# usb_dip_v1.net
KiCad netlist of a schematic drawn in EAGLE
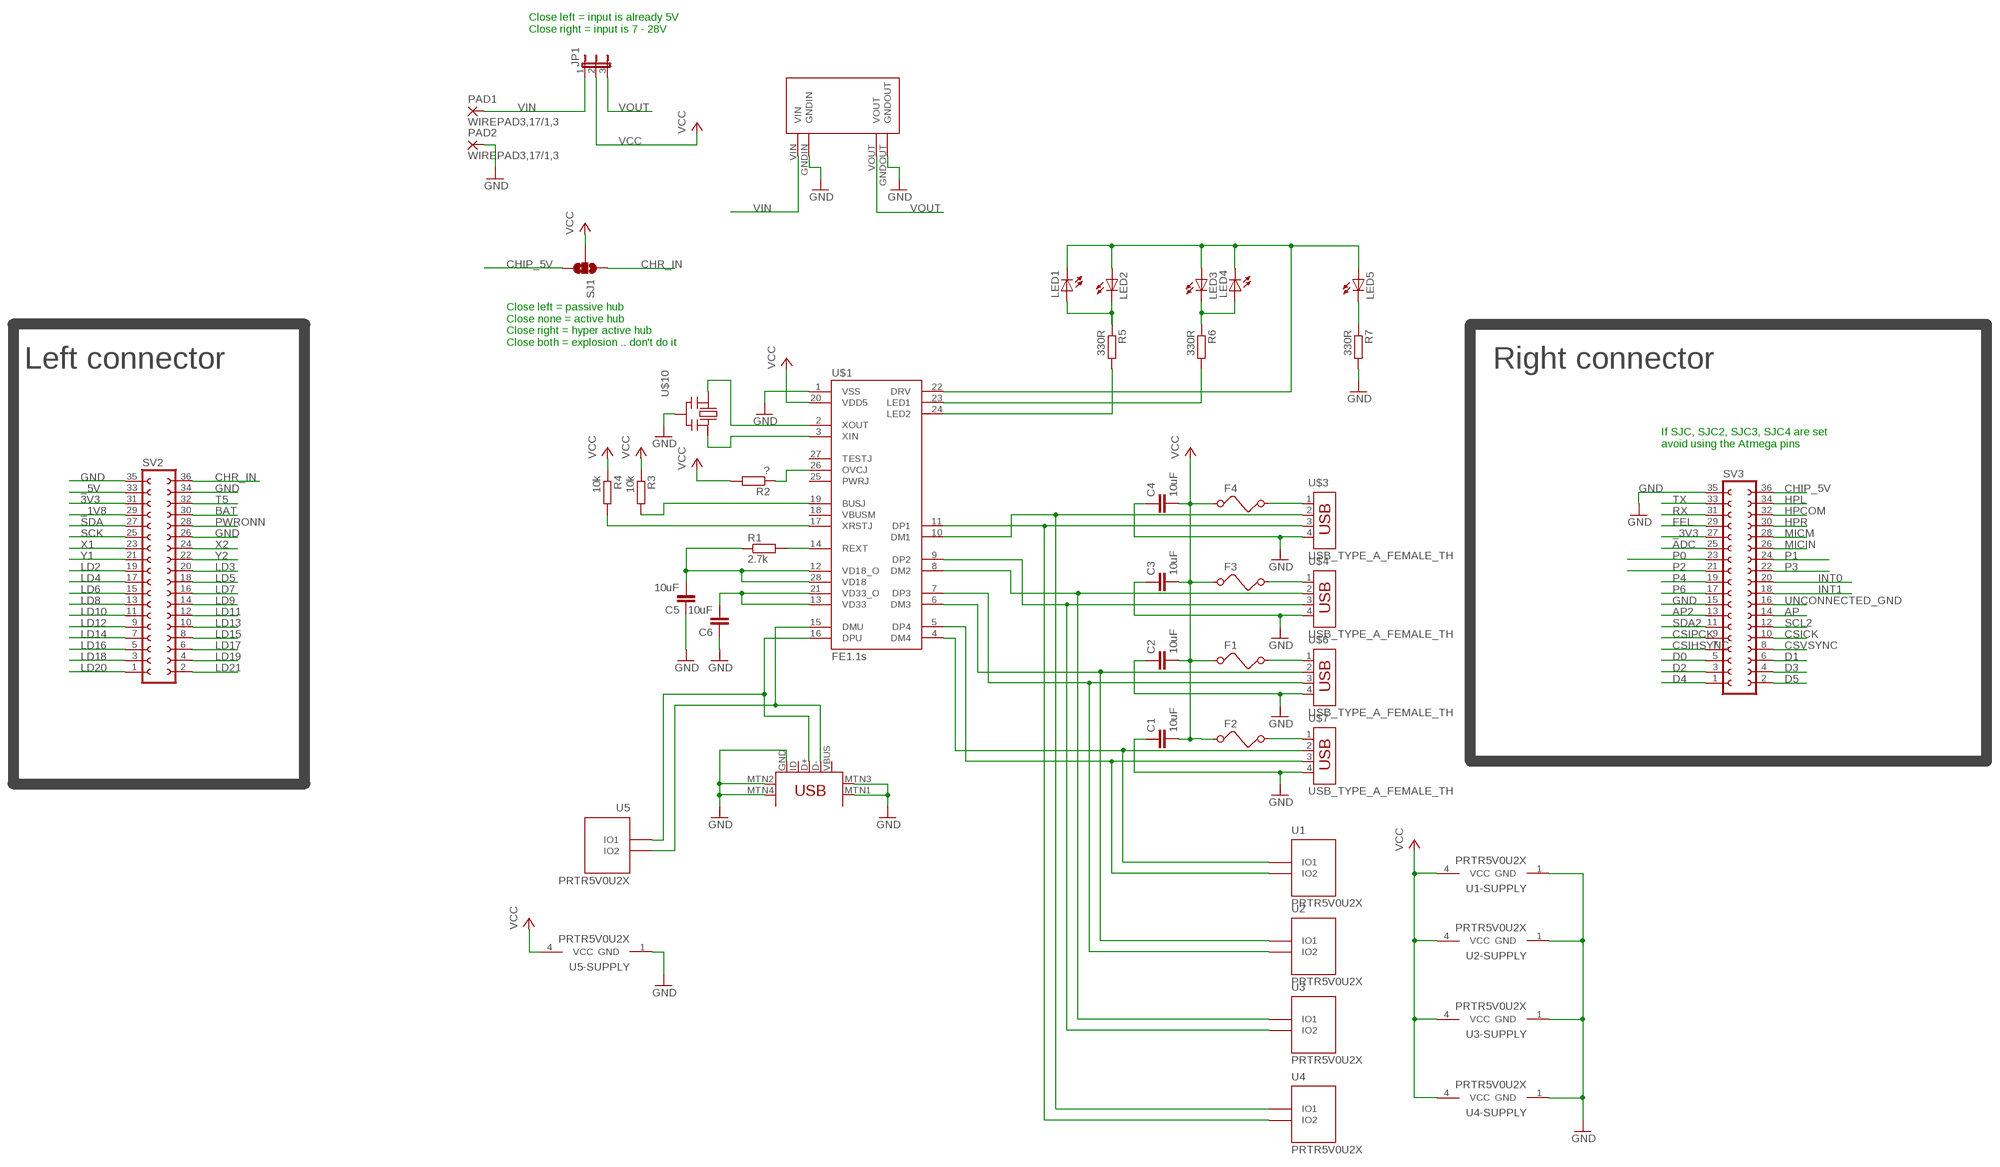
[diagram p0: schematic, sheet 1]

(export (version "E")
  (design (tool "Eeschema 10.0.6"))
  (components
    (comp (ref "C1")
      (value "10uF")
      (footprint "eagle-import:C1210")
      (libsource (lib "eagle-import") (part "C-EUC1210"))
    )
    (comp (ref "C2")
      (value "10uF")
      (footprint "eagle-import:C1210")
      (libsource (lib "eagle-import") (part "C-EUC1210"))
    )
    (comp (ref "C3")
      (value "10uF")
      (footprint "eagle-import:C1210")
      (libsource (lib "eagle-import") (part "C-EUC1210"))
    )
    (comp (ref "C4")
      (value "10uF")
      (footprint "eagle-import:C1210")
      (libsource (lib "eagle-import") (part "C-EUC1210"))
    )
    (comp (ref "C5")
      (value "10uF")
      (footprint "eagle-import:C1210")
      (libsource (lib "eagle-import") (part "C-EUC1210"))
    )
    (comp (ref "C6")
      (value "10uF")
      (footprint "eagle-import:C1210")
      (libsource (lib "eagle-import") (part "C-EUC1210"))
    )
    (comp (ref "F1")
      (value "FUSED")
      (footprint "eagle-import:1210")
      (libsource (lib "eagle-import") (part "FUSED"))
    )
    (comp (ref "F2")
      (value "FUSED")
      (footprint "eagle-import:1210")
      (libsource (lib "eagle-import") (part "FUSED"))
    )
    (comp (ref "F3")
      (value "FUSED")
      (footprint "eagle-import:1210")
      (libsource (lib "eagle-import") (part "FUSED"))
    )
    (comp (ref "F4")
      (value "FUSED")
      (footprint "eagle-import:1210")
      (libsource (lib "eagle-import") (part "FUSED"))
    )
    (comp (ref "JP1")
      (value "JP2E")
      (footprint "eagle-import:JP2")
      (libsource (lib "eagle-import") (part "JP2E"))
    )
    (comp (ref "LED1")
      (value "LEDCHIP-LED0805")
      (footprint "eagle-import:CHIP-LED0805")
      (libsource (lib "eagle-import") (part "LEDCHIP-LED0805"))
    )
    (comp (ref "LED2")
      (value "LEDCHIP-LED0805")
      (footprint "eagle-import:CHIP-LED0805")
      (libsource (lib "eagle-import") (part "LEDCHIP-LED0805"))
    )
    (comp (ref "LED3")
      (value "LEDCHIP-LED0805")
      (footprint "eagle-import:CHIP-LED0805")
      (libsource (lib "eagle-import") (part "LEDCHIP-LED0805"))
    )
    (comp (ref "LED4")
      (value "LEDCHIP-LED0805")
      (footprint "eagle-import:CHIP-LED0805")
      (libsource (lib "eagle-import") (part "LEDCHIP-LED0805"))
    )
    (comp (ref "LED5")
      (value "LEDCHIP-LED0805")
      (footprint "eagle-import:CHIP-LED0805")
      (libsource (lib "eagle-import") (part "LEDCHIP-LED0805"))
    )
    (comp (ref "PAD1")
      (value "WIREPAD3,17/1,3")
      (footprint "eagle-import:3,17_1,3")
      (libsource (lib "eagle-import") (part "WIREPAD3,17/1,3"))
    )
    (comp (ref "PAD2")
      (value "WIREPAD3,17/1,3")
      (footprint "eagle-import:3,17_1,3")
      (libsource (lib "eagle-import") (part "WIREPAD3,17/1,3"))
    )
    (comp (ref "R1")
      (value "2.7k")
      (footprint "eagle-import:R0805")
      (libsource (lib "eagle-import") (part "R-EU_R0805"))
    )
    (comp (ref "R2")
      (value "?")
      (footprint "eagle-import:R0805")
      (libsource (lib "eagle-import") (part "R-EU_R0805"))
    )
    (comp (ref "R3")
      (value "10k")
      (footprint "eagle-import:R0805")
      (libsource (lib "eagle-import") (part "R-EU_R0805"))
    )
    (comp (ref "R4")
      (value "10k")
      (footprint "eagle-import:R0805")
      (libsource (lib "eagle-import") (part "R-EU_R0805"))
    )
    (comp (ref "R5")
      (value "330R")
      (footprint "eagle-import:R0805")
      (libsource (lib "eagle-import") (part "R-EU_R0805"))
    )
    (comp (ref "R6")
      (value "330R")
      (footprint "eagle-import:R0805")
      (libsource (lib "eagle-import") (part "R-EU_R0805"))
    )
    (comp (ref "R7")
      (value "330R")
      (footprint "eagle-import:R0805")
      (libsource (lib "eagle-import") (part "R-EU_R0805"))
    )
    (comp (ref "SJ1")
      (value "SOLDERJUMPER_2WAYT")
      (footprint "eagle-import:SJ_2")
      (libsource (lib "eagle-import") (part "SOLDERJUMPER_2WAYT"))
    )
    (comp (ref "SV2")
      (value "FE18-2")
      (footprint "eagle-import:FE18-2")
      (libsource (lib "eagle-import") (part "FE18-2"))
    )
    (comp (ref "SV3")
      (value "FE18-2")
      (footprint "eagle-import:FE18-2")
      (libsource (lib "eagle-import") (part "FE18-2"))
    )
    (comp (ref "U$1")
      (value "FE1.1S")
      (footprint "eagle-import:FE1.1S_SSOP-28")
      (libsource (lib "eagle-import") (part "FE1.1S"))
    )
    (comp (ref "U$3")
      (value "USB_TYPE_A_FEMALE_TH")
      (footprint "eagle-import:USB_TYPE_A_FEMALE_TH")
      (libsource (lib "eagle-import") (part "USB_TYPE_A_FEMALE_TH"))
    )
    (comp (ref "U$4")
      (value "USB_TYPE_A_FEMALE_TH")
      (footprint "eagle-import:USB_TYPE_A_FEMALE_TH")
      (libsource (lib "eagle-import") (part "USB_TYPE_A_FEMALE_TH"))
    )
    (comp (ref "U$6")
      (value "USB_TYPE_A_FEMALE_TH")
      (footprint "eagle-import:USB_TYPE_A_FEMALE_TH")
      (libsource (lib "eagle-import") (part "USB_TYPE_A_FEMALE_TH"))
    )
    (comp (ref "U$7")
      (value "USB_TYPE_A_FEMALE_TH")
      (footprint "eagle-import:USB_TYPE_A_FEMALE_TH")
      (libsource (lib "eagle-import") (part "USB_TYPE_A_FEMALE_TH"))
    )
    (comp (ref "U$8")
      (value "USB-MINIB-5PIN")
      (footprint "eagle-import:USB-MINIB")
      (libsource (lib "eagle-import") (part "USB-MINIB-5PIN"))
    )
    (comp (ref "U$9")
      (value "MP1584EN")
      (footprint "eagle-import:MP1584EN")
      (libsource (lib "eagle-import") (part "MP1584EN"))
    )
    (comp (ref "U$10")
      (value "CERMOSCILL-THM")
      (footprint "eagle-import:CERM_OSC")
      (libsource (lib "eagle-import") (part "CERMOSCILL-THM"))
    )
    (comp (ref "U1")
      (value "PRTR5V0U2X")
      (footprint "eagle-import:SOT-143B")
      (fields
        (field (name "MANUFACTURER") "NXP Semiconductors")
        (field (name "PART_NUMBER") "PRTR5V0U2X,215")
      )
      (libsource (lib "eagle-import") (part "PRTR5V0U2X?"))
    )
    (comp (ref "U2")
      (value "PRTR5V0U2X")
      (footprint "eagle-import:SOT-143B")
      (fields
        (field (name "MANUFACTURER") "NXP Semiconductors")
        (field (name "PART_NUMBER") "PRTR5V0U2X,215")
      )
      (libsource (lib "eagle-import") (part "PRTR5V0U2X?"))
    )
    (comp (ref "U3")
      (value "PRTR5V0U2X")
      (footprint "eagle-import:SOT-143B")
      (fields
        (field (name "MANUFACTURER") "NXP Semiconductors")
        (field (name "PART_NUMBER") "PRTR5V0U2X,215")
      )
      (libsource (lib "eagle-import") (part "PRTR5V0U2X?"))
    )
    (comp (ref "U4")
      (value "PRTR5V0U2X")
      (footprint "eagle-import:SOT-143B")
      (fields
        (field (name "MANUFACTURER") "NXP Semiconductors")
        (field (name "PART_NUMBER") "PRTR5V0U2X,215")
      )
      (libsource (lib "eagle-import") (part "PRTR5V0U2X?"))
    )
    (comp (ref "U5")
      (value "PRTR5V0U2X")
      (footprint "eagle-import:SOT-143B")
      (fields
        (field (name "MANUFACTURER") "NXP Semiconductors")
        (field (name "PART_NUMBER") "PRTR5V0U2X,215")
      )
      (libsource (lib "eagle-import") (part "PRTR5V0U2X?"))
    )
  )
  (nets
    (net (code "1") (name "/3V3") (class "Default")
      (node (ref "SV2") (pin "31") (pinfunction "31_31") (pintype "passive"))
    )
    (net (code "2") (name "/ADC") (class "Default")
      (node (ref "SV3") (pin "25") (pinfunction "25_25") (pintype "passive"))
    )
    (net (code "3") (name "/AP") (class "Default")
      (node (ref "SV3") (pin "14") (pinfunction "14_14") (pintype "passive"))
    )
    (net (code "4") (name "/AP2") (class "Default")
      (node (ref "SV3") (pin "13") (pinfunction "13_13") (pintype "passive"))
    )
    (net (code "5") (name "/BAT") (class "Default")
      (node (ref "SV2") (pin "30") (pinfunction "30_30") (pintype "passive"))
    )
    (net (code "6") (name "/CHIP_5V") (class "Default")
      (node (ref "SJ1") (pin "3") (pinfunction "3_3") (pintype "passive"))
      (node (ref "SV3") (pin "36") (pinfunction "36_36") (pintype "passive"))
    )
    (net (code "7") (name "/CHR_IN") (class "Default")
      (node (ref "SJ1") (pin "1") (pinfunction "1_1") (pintype "passive"))
      (node (ref "SV2") (pin "36") (pinfunction "36_36") (pintype "passive"))
    )
    (net (code "8") (name "/CSICK") (class "Default")
      (node (ref "SV3") (pin "10") (pinfunction "10_10") (pintype "passive"))
    )
    (net (code "9") (name "/CSIHSYNC") (class "Default")
      (node (ref "SV3") (pin "7") (pinfunction "7_7") (pintype "passive"))
    )
    (net (code "10") (name "/CSIPCK") (class "Default")
      (node (ref "SV3") (pin "9") (pinfunction "9_9") (pintype "passive"))
    )
    (net (code "11") (name "/CSVSYNC") (class "Default")
      (node (ref "SV3") (pin "8") (pinfunction "8_8") (pintype "passive"))
    )
    (net (code "12") (name "/D0") (class "Default")
      (node (ref "SV3") (pin "5") (pinfunction "5_5") (pintype "passive"))
    )
    (net (code "13") (name "/D1") (class "Default")
      (node (ref "SV3") (pin "6") (pinfunction "6_6") (pintype "passive"))
    )
    (net (code "14") (name "/D2") (class "Default")
      (node (ref "SV3") (pin "3") (pinfunction "3_3") (pintype "passive"))
    )
    (net (code "15") (name "/D3") (class "Default")
      (node (ref "SV3") (pin "4") (pinfunction "4_4") (pintype "passive"))
    )
    (net (code "16") (name "/D4") (class "Default")
      (node (ref "SV3") (pin "1") (pinfunction "1_1") (pintype "passive"))
    )
    (net (code "17") (name "/D5") (class "Default")
      (node (ref "SV3") (pin "2") (pinfunction "2_2") (pintype "passive"))
    )
    (net (code "18") (name "/FEL") (class "Default")
      (node (ref "SV3") (pin "29") (pinfunction "29_29") (pintype "passive"))
    )
    (net (code "19") (name "/HPCOM") (class "Default")
      (node (ref "SV3") (pin "32") (pinfunction "32_32") (pintype "passive"))
    )
    (net (code "20") (name "/HPL") (class "Default")
      (node (ref "SV3") (pin "34") (pinfunction "34_34") (pintype "passive"))
    )
    (net (code "21") (name "/HPR") (class "Default")
      (node (ref "SV3") (pin "30") (pinfunction "30_30") (pintype "passive"))
    )
    (net (code "22") (name "/INT0") (class "Default")
      (node (ref "SV3") (pin "20") (pinfunction "20_20") (pintype "passive"))
    )
    (net (code "23") (name "/INT1") (class "Default")
      (node (ref "SV3") (pin "18") (pinfunction "18_18") (pintype "passive"))
    )
    (net (code "24") (name "/LD2") (class "Default")
      (node (ref "SV2") (pin "19") (pinfunction "19_19") (pintype "passive"))
    )
    (net (code "25") (name "/LD3") (class "Default")
      (node (ref "SV2") (pin "20") (pinfunction "20_20") (pintype "passive"))
    )
    (net (code "26") (name "/LD4") (class "Default")
      (node (ref "SV2") (pin "17") (pinfunction "17_17") (pintype "passive"))
    )
    (net (code "27") (name "/LD5") (class "Default")
      (node (ref "SV2") (pin "18") (pinfunction "18_18") (pintype "passive"))
    )
    (net (code "28") (name "/LD6") (class "Default")
      (node (ref "SV2") (pin "15") (pinfunction "15_15") (pintype "passive"))
    )
    (net (code "29") (name "/LD7") (class "Default")
      (node (ref "SV2") (pin "16") (pinfunction "16_16") (pintype "passive"))
    )
    (net (code "30") (name "/LD8") (class "Default")
      (node (ref "SV2") (pin "13") (pinfunction "13_13") (pintype "passive"))
    )
    (net (code "31") (name "/LD9") (class "Default")
      (node (ref "SV2") (pin "14") (pinfunction "14_14") (pintype "passive"))
    )
    (net (code "32") (name "/LD10") (class "Default")
      (node (ref "SV2") (pin "11") (pinfunction "11_11") (pintype "passive"))
    )
    (net (code "33") (name "/LD11") (class "Default")
      (node (ref "SV2") (pin "12") (pinfunction "12_12") (pintype "passive"))
    )
    (net (code "34") (name "/LD12") (class "Default")
      (node (ref "SV2") (pin "9") (pinfunction "9_9") (pintype "passive"))
    )
    (net (code "35") (name "/LD13") (class "Default")
      (node (ref "SV2") (pin "10") (pinfunction "10_10") (pintype "passive"))
    )
    (net (code "36") (name "/LD14") (class "Default")
      (node (ref "SV2") (pin "7") (pinfunction "7_7") (pintype "passive"))
    )
    (net (code "37") (name "/LD15") (class "Default")
      (node (ref "SV2") (pin "8") (pinfunction "8_8") (pintype "passive"))
    )
    (net (code "38") (name "/LD16") (class "Default")
      (node (ref "SV2") (pin "5") (pinfunction "5_5") (pintype "passive"))
    )
    (net (code "39") (name "/LD17") (class "Default")
      (node (ref "SV2") (pin "6") (pinfunction "6_6") (pintype "passive"))
    )
    (net (code "40") (name "/LD18") (class "Default")
      (node (ref "SV2") (pin "3") (pinfunction "3_3") (pintype "passive"))
    )
    (net (code "41") (name "/LD19") (class "Default")
      (node (ref "SV2") (pin "4") (pinfunction "4_4") (pintype "passive"))
    )
    (net (code "42") (name "/LD20") (class "Default")
      (node (ref "SV2") (pin "1") (pinfunction "1_1") (pintype "passive"))
    )
    (net (code "43") (name "/LD21") (class "Default")
      (node (ref "SV2") (pin "2") (pinfunction "2_2") (pintype "passive"))
    )
    (net (code "44") (name "/MICIN") (class "Default")
      (node (ref "SV3") (pin "26") (pinfunction "26_26") (pintype "passive"))
    )
    (net (code "45") (name "/MICM") (class "Default")
      (node (ref "SV3") (pin "28") (pinfunction "28_28") (pintype "passive"))
    )
    (net (code "46") (name "/P0") (class "Default")
      (node (ref "SV3") (pin "23") (pinfunction "23_23") (pintype "passive"))
    )
    (net (code "47") (name "/P1") (class "Default")
      (node (ref "SV3") (pin "24") (pinfunction "24_24") (pintype "passive"))
    )
    (net (code "48") (name "/P2") (class "Default")
      (node (ref "SV3") (pin "21") (pinfunction "21_21") (pintype "passive"))
    )
    (net (code "49") (name "/P3") (class "Default")
      (node (ref "SV3") (pin "22") (pinfunction "22_22") (pintype "passive"))
    )
    (net (code "50") (name "/P4") (class "Default")
      (node (ref "SV3") (pin "19") (pinfunction "19_19") (pintype "passive"))
    )
    (net (code "51") (name "/P6") (class "Default")
      (node (ref "SV3") (pin "17") (pinfunction "17_17") (pintype "passive"))
    )
    (net (code "52") (name "/PWRONN") (class "Default")
      (node (ref "SV2") (pin "28") (pinfunction "28_28") (pintype "passive"))
    )
    (net (code "53") (name "/RX") (class "Default")
      (node (ref "SV3") (pin "31") (pinfunction "31_31") (pintype "passive"))
    )
    (net (code "54") (name "/SCK") (class "Default")
      (node (ref "SV2") (pin "25") (pinfunction "25_25") (pintype "passive"))
    )
    (net (code "55") (name "/SCL2") (class "Default")
      (node (ref "SV3") (pin "12") (pinfunction "12_12") (pintype "passive"))
    )
    (net (code "56") (name "/SDA") (class "Default")
      (node (ref "SV2") (pin "27") (pinfunction "27_27") (pintype "passive"))
    )
    (net (code "57") (name "/SDA2") (class "Default")
      (node (ref "SV3") (pin "11") (pinfunction "11_11") (pintype "passive"))
    )
    (net (code "58") (name "/T5") (class "Default")
      (node (ref "SV2") (pin "32") (pinfunction "32_32") (pintype "passive"))
    )
    (net (code "59") (name "/TX") (class "Default")
      (node (ref "SV3") (pin "33") (pinfunction "33_33") (pintype "passive"))
    )
    (net (code "60") (name "/UNCONNECTED_GND") (class "Default")
      (node (ref "SV3") (pin "16") (pinfunction "16_16") (pintype "passive"))
    )
    (net (code "61") (name "/VIN") (class "Default")
      (node (ref "JP1") (pin "1") (pinfunction "1_1") (pintype "passive"))
      (node (ref "PAD1") (pin "1") (pinfunction "P_1") (pintype "passive"))
      (node (ref "U$9") (pin "VIN") (pinfunction "VIN_VIN") (pintype "power_in"))
    )
    (net (code "62") (name "/VOUT") (class "Default")
      (node (ref "JP1") (pin "3") (pinfunction "3_3") (pintype "passive"))
      (node (ref "U$9") (pin "VOUT") (pinfunction "VOUT_VOUT") (pintype "power_in"))
    )
    (net (code "63") (name "/X1") (class "Default")
      (node (ref "SV2") (pin "23") (pinfunction "23_23") (pintype "passive"))
    )
    (net (code "64") (name "/X2") (class "Default")
      (node (ref "SV2") (pin "24") (pinfunction "24_24") (pintype "passive"))
    )
    (net (code "65") (name "/Y1") (class "Default")
      (node (ref "SV2") (pin "21") (pinfunction "21_21") (pintype "passive"))
    )
    (net (code "66") (name "/Y2") (class "Default")
      (node (ref "SV2") (pin "22") (pinfunction "22_22") (pintype "passive"))
    )
    (net (code "67") (name "/_1V8") (class "Default")
      (node (ref "SV2") (pin "29") (pinfunction "29_29") (pintype "passive"))
    )
    (net (code "68") (name "/_3V3") (class "Default")
      (node (ref "SV3") (pin "27") (pinfunction "27_27") (pintype "passive"))
    )
    (net (code "69") (name "/_5V") (class "Default")
      (node (ref "SV2") (pin "33") (pinfunction "33_33") (pintype "passive"))
    )
    (net (code "70") (name "GND") (class "Default")
      (node (ref "C1") (pin "1") (pinfunction "1_1") (pintype "passive"))
      (node (ref "C2") (pin "1") (pinfunction "1_1") (pintype "passive"))
      (node (ref "C3") (pin "1") (pinfunction "1_1") (pintype "passive"))
      (node (ref "C4") (pin "1") (pinfunction "1_1") (pintype "passive"))
      (node (ref "C5") (pin "1") (pinfunction "1_1") (pintype "passive"))
      (node (ref "C6") (pin "1") (pinfunction "1_1") (pintype "passive"))
      (node (ref "PAD2") (pin "1") (pinfunction "P_1") (pintype "passive"))
      (node (ref "R7") (pin "2") (pinfunction "2_2") (pintype "passive"))
      (node (ref "SV2") (pin "26") (pinfunction "26_26") (pintype "passive"))
      (node (ref "SV2") (pin "34") (pinfunction "34_34") (pintype "passive"))
      (node (ref "SV2") (pin "35") (pinfunction "35_35") (pintype "passive"))
      (node (ref "SV3") (pin "15") (pinfunction "15_15") (pintype "passive"))
      (node (ref "SV3") (pin "35") (pinfunction "35_35") (pintype "passive"))
      (node (ref "U$1") (pin "1") (pinfunction "VSS_1") (pintype "bidirectional"))
      (node (ref "U$10") (pin "P$2") (pinfunction "GND_P$2") (pintype "bidirectional"))
      (node (ref "U$3") (pin "4") (pinfunction "4_4") (pintype "passive"))
      (node (ref "U$4") (pin "4") (pinfunction "4_4") (pintype "passive"))
      (node (ref "U$6") (pin "4") (pinfunction "4_4") (pintype "passive"))
      (node (ref "U$7") (pin "4") (pinfunction "4_4") (pintype "passive"))
      (node (ref "U$8") (pin "GND") (pinfunction "GND_GND") (pintype "bidirectional"))
      (node (ref "U$8") (pin "MTN1") (pinfunction "MTN2_MTN1") (pintype "bidirectional"))
      (node (ref "U$8") (pin "MTN2") (pinfunction "MTN3_MTN2") (pintype "bidirectional"))
      (node (ref "U$8") (pin "MTN3") (pinfunction "MTN1_MTN3") (pintype "bidirectional"))
      (node (ref "U$8") (pin "MTN4") (pinfunction "MTN4_MTN4") (pintype "bidirectional"))
      (node (ref "U$9") (pin "GNDIN") (pinfunction "GNDIN_GNDIN") (pintype "power_in"))
      (node (ref "U$9") (pin "GNDOUT") (pinfunction "GNDOUT_GNDOUT") (pintype "power_in"))
      (node (ref "U1") (pin "1") (pinfunction "GND_1") (pintype "bidirectional"))
      (node (ref "U2") (pin "1") (pinfunction "GND_1") (pintype "bidirectional"))
      (node (ref "U3") (pin "1") (pinfunction "GND_1") (pintype "bidirectional"))
      (node (ref "U4") (pin "1") (pinfunction "GND_1") (pintype "bidirectional"))
      (node (ref "U5") (pin "1") (pinfunction "GND_1") (pintype "bidirectional"))
    )
    (net (code "71") (name "Net-(F1-Pad2)") (class "Default")
      (node (ref "F1") (pin "2") (pinfunction "2_2") (pintype "passive"))
      (node (ref "U$6") (pin "1") (pinfunction "1_1") (pintype "passive"))
    )
    (net (code "72") (name "Net-(F2-Pad2)") (class "Default")
      (node (ref "F2") (pin "2") (pinfunction "2_2") (pintype "passive"))
      (node (ref "U$7") (pin "1") (pinfunction "1_1") (pintype "passive"))
    )
    (net (code "73") (name "Net-(F3-Pad2)") (class "Default")
      (node (ref "F3") (pin "2") (pinfunction "2_2") (pintype "passive"))
      (node (ref "U$4") (pin "1") (pinfunction "1_1") (pintype "passive"))
    )
    (net (code "74") (name "Net-(F4-Pad2)") (class "Default")
      (node (ref "F4") (pin "2") (pinfunction "2_2") (pintype "passive"))
      (node (ref "U$3") (pin "1") (pinfunction "1_1") (pintype "passive"))
    )
    (net (code "75") (name "Net-(LED1-PadA)") (class "Default")
      (node (ref "LED1") (pin "A") (pinfunction "A_A") (pintype "passive"))
      (node (ref "LED2") (pin "C") (pinfunction "C_C") (pintype "passive"))
      (node (ref "R5") (pin "1") (pinfunction "1_1") (pintype "passive"))
    )
    (net (code "76") (name "Net-(LED3-PadC)") (class "Default")
      (node (ref "LED3") (pin "C") (pinfunction "C_C") (pintype "passive"))
      (node (ref "LED4") (pin "A") (pinfunction "A_A") (pintype "passive"))
      (node (ref "R6") (pin "1") (pinfunction "1_1") (pintype "passive"))
    )
    (net (code "77") (name "Net-(LED5-PadC)") (class "Default")
      (node (ref "LED5") (pin "C") (pinfunction "C_C") (pintype "passive"))
      (node (ref "R7") (pin "1") (pinfunction "1_1") (pintype "passive"))
    )
    (net (code "78") (name "Net-(U$1-BUSJ)") (class "Default")
      (node (ref "R3") (pin "2") (pinfunction "2_2") (pintype "passive"))
      (node (ref "U$1") (pin "19") (pinfunction "BUSJ_19") (pintype "bidirectional"))
    )
    (net (code "79") (name "Net-(U$1-DM1)") (class "Default")
      (node (ref "U$1") (pin "10") (pinfunction "DM1_10") (pintype "bidirectional"))
      (node (ref "U$3") (pin "2") (pinfunction "2_2") (pintype "passive"))
      (node (ref "U4") (pin "2") (pinfunction "IO1_2") (pintype "bidirectional"))
    )
    (net (code "80") (name "Net-(U$1-DM2)") (class "Default")
      (node (ref "U$1") (pin "8") (pinfunction "DM2_8") (pintype "bidirectional"))
      (node (ref "U$4") (pin "2") (pinfunction "2_2") (pintype "passive"))
      (node (ref "U3") (pin "2") (pinfunction "IO1_2") (pintype "bidirectional"))
    )
    (net (code "81") (name "Net-(U$1-DM3)") (class "Default")
      (node (ref "U$1") (pin "6") (pinfunction "DM3_6") (pintype "bidirectional"))
      (node (ref "U$6") (pin "2") (pinfunction "2_2") (pintype "passive"))
      (node (ref "U2") (pin "2") (pinfunction "IO1_2") (pintype "bidirectional"))
    )
    (net (code "82") (name "Net-(U$1-DM4)") (class "Default")
      (node (ref "U$1") (pin "4") (pinfunction "DM4_4") (pintype "bidirectional"))
      (node (ref "U$7") (pin "2") (pinfunction "2_2") (pintype "passive"))
      (node (ref "U1") (pin "2") (pinfunction "IO1_2") (pintype "bidirectional"))
    )
    (net (code "83") (name "Net-(U$1-DMU)") (class "Default")
      (node (ref "U$1") (pin "15") (pinfunction "DMU_15") (pintype "bidirectional"))
      (node (ref "U$8") (pin "D-") (pinfunction "D-_D-") (pintype "bidirectional"))
      (node (ref "U5") (pin "3") (pinfunction "IO2_3") (pintype "bidirectional"))
    )
    (net (code "84") (name "Net-(U$1-DP1)") (class "Default")
      (node (ref "U$1") (pin "11") (pinfunction "DP1_11") (pintype "bidirectional"))
      (node (ref "U$3") (pin "3") (pinfunction "3_3") (pintype "passive"))
      (node (ref "U4") (pin "3") (pinfunction "IO2_3") (pintype "bidirectional"))
    )
    (net (code "85") (name "Net-(U$1-DP2)") (class "Default")
      (node (ref "U$1") (pin "9") (pinfunction "DP2_9") (pintype "bidirectional"))
      (node (ref "U$4") (pin "3") (pinfunction "3_3") (pintype "passive"))
      (node (ref "U3") (pin "3") (pinfunction "IO2_3") (pintype "bidirectional"))
    )
    (net (code "86") (name "Net-(U$1-DP3)") (class "Default")
      (node (ref "U$1") (pin "7") (pinfunction "DP3_7") (pintype "bidirectional"))
      (node (ref "U$6") (pin "3") (pinfunction "3_3") (pintype "passive"))
      (node (ref "U2") (pin "3") (pinfunction "IO2_3") (pintype "bidirectional"))
    )
    (net (code "87") (name "Net-(U$1-DP4)") (class "Default")
      (node (ref "U$1") (pin "5") (pinfunction "DP4_5") (pintype "bidirectional"))
      (node (ref "U$7") (pin "3") (pinfunction "3_3") (pintype "passive"))
      (node (ref "U1") (pin "3") (pinfunction "IO2_3") (pintype "bidirectional"))
    )
    (net (code "88") (name "Net-(U$1-DPU)") (class "Default")
      (node (ref "U$1") (pin "16") (pinfunction "DPU_16") (pintype "bidirectional"))
      (node (ref "U$8") (pin "D+") (pinfunction "D+_D+") (pintype "bidirectional"))
      (node (ref "U5") (pin "2") (pinfunction "IO1_2") (pintype "bidirectional"))
    )
    (net (code "89") (name "Net-(U$1-DRV)") (class "Default")
      (node (ref "LED1") (pin "C") (pinfunction "C_C") (pintype "passive"))
      (node (ref "LED2") (pin "A") (pinfunction "A_A") (pintype "passive"))
      (node (ref "LED3") (pin "A") (pinfunction "A_A") (pintype "passive"))
      (node (ref "LED4") (pin "C") (pinfunction "C_C") (pintype "passive"))
      (node (ref "LED5") (pin "A") (pinfunction "A_A") (pintype "passive"))
      (node (ref "U$1") (pin "22") (pinfunction "DRV_22") (pintype "bidirectional"))
    )
    (net (code "90") (name "Net-(U$1-LED1)") (class "Default")
      (node (ref "R6") (pin "2") (pinfunction "2_2") (pintype "passive"))
      (node (ref "U$1") (pin "23") (pinfunction "LED1_23") (pintype "bidirectional"))
    )
    (net (code "91") (name "Net-(U$1-LED2)") (class "Default")
      (node (ref "R5") (pin "2") (pinfunction "2_2") (pintype "passive"))
      (node (ref "U$1") (pin "24") (pinfunction "LED2_24") (pintype "bidirectional"))
    )
    (net (code "92") (name "Net-(U$1-OVCJ)") (class "Default")
      (node (ref "R2") (pin "1") (pinfunction "1_1") (pintype "passive"))
      (node (ref "U$1") (pin "26") (pinfunction "OVCJ_26") (pintype "bidirectional"))
    )
    (net (code "93") (name "Net-(U$1-REXT)") (class "Default")
      (node (ref "R1") (pin "2") (pinfunction "2_2") (pintype "passive"))
      (node (ref "U$1") (pin "14") (pinfunction "REXT_14") (pintype "bidirectional"))
    )
    (net (code "94") (name "Net-(U$1-VD18)") (class "Default")
      (node (ref "C5") (pin "2") (pinfunction "2_2") (pintype "passive"))
      (node (ref "R1") (pin "1") (pinfunction "1_1") (pintype "passive"))
      (node (ref "U$1") (pin "12") (pinfunction "VD18_O_12") (pintype "bidirectional"))
      (node (ref "U$1") (pin "28") (pinfunction "VD18_28") (pintype "bidirectional"))
    )
    (net (code "95") (name "Net-(U$1-VD33)") (class "Default")
      (node (ref "C6") (pin "2") (pinfunction "2_2") (pintype "passive"))
      (node (ref "U$1") (pin "13") (pinfunction "VD33_13") (pintype "bidirectional"))
      (node (ref "U$1") (pin "21") (pinfunction "VD33_O_21") (pintype "bidirectional"))
    )
    (net (code "96") (name "Net-(U$1-XIN)") (class "Default")
      (node (ref "U$1") (pin "3") (pinfunction "XIN_3") (pintype "bidirectional"))
      (node (ref "U$10") (pin "P$3") (pinfunction "OUT_P$3") (pintype "bidirectional"))
    )
    (net (code "97") (name "Net-(U$1-XOUT)") (class "Default")
      (node (ref "U$1") (pin "2") (pinfunction "XOUT_2") (pintype "bidirectional"))
      (node (ref "U$10") (pin "P$1") (pinfunction "IN_P$1") (pintype "bidirectional"))
    )
    (net (code "98") (name "Net-(U$1-XRSTJ)") (class "Default")
      (node (ref "R4") (pin "2") (pinfunction "2_2") (pintype "passive"))
      (node (ref "U$1") (pin "17") (pinfunction "XRSTJ_17") (pintype "bidirectional"))
    )
    (net (code "99") (name "VCC") (class "Default")
      (node (ref "C1") (pin "2") (pinfunction "2_2") (pintype "passive"))
      (node (ref "C2") (pin "2") (pinfunction "2_2") (pintype "passive"))
      (node (ref "C3") (pin "2") (pinfunction "2_2") (pintype "passive"))
      (node (ref "C4") (pin "2") (pinfunction "2_2") (pintype "passive"))
      (node (ref "F1") (pin "1") (pinfunction "1_1") (pintype "passive"))
      (node (ref "F2") (pin "1") (pinfunction "1_1") (pintype "passive"))
      (node (ref "F3") (pin "1") (pinfunction "1_1") (pintype "passive"))
      (node (ref "F4") (pin "1") (pinfunction "1_1") (pintype "passive"))
      (node (ref "JP1") (pin "2") (pinfunction "2_2") (pintype "passive"))
      (node (ref "R2") (pin "2") (pinfunction "2_2") (pintype "passive"))
      (node (ref "R3") (pin "1") (pinfunction "1_1") (pintype "passive"))
      (node (ref "R4") (pin "1") (pinfunction "1_1") (pintype "passive"))
      (node (ref "SJ1") (pin "2") (pinfunction "2_2") (pintype "passive"))
      (node (ref "U$1") (pin "20") (pinfunction "VDD5_20") (pintype "bidirectional"))
      (node (ref "U1") (pin "4") (pinfunction "VCC_4") (pintype "bidirectional"))
      (node (ref "U2") (pin "4") (pinfunction "VCC_4") (pintype "bidirectional"))
      (node (ref "U3") (pin "4") (pinfunction "VCC_4") (pintype "bidirectional"))
      (node (ref "U4") (pin "4") (pinfunction "VCC_4") (pintype "bidirectional"))
      (node (ref "U5") (pin "4") (pinfunction "VCC_4") (pintype "bidirectional"))
    )
    (net (code "100") (name "unconnected-(U$1-PWRJ-Pad25)") (class "Default")
      (node (ref "U$1") (pin "25") (pinfunction "PWRJ_25") (pintype "bidirectional"))
    )
    (net (code "101") (name "unconnected-(U$1-TESTJ-Pad27)") (class "Default")
      (node (ref "U$1") (pin "27") (pinfunction "TESTJ_27") (pintype "bidirectional"))
    )
    (net (code "102") (name "unconnected-(U$1-VBUSM-Pad18)") (class "Default")
      (node (ref "U$1") (pin "18") (pinfunction "VBUSM_18") (pintype "bidirectional"))
    )
    (net (code "103") (name "unconnected-(U$8-PadID)") (class "Default")
      (node (ref "U$8") (pin "ID") (pinfunction "ID_ID") (pintype "bidirectional"))
    )
    (net (code "104") (name "unconnected-(U$8-PadVBUS)") (class "Default")
      (node (ref "U$8") (pin "VBUS") (pinfunction "VBUS_VBUS") (pintype "bidirectional"))
    )
  )
)
